# Transformer.net
KiCad netlist of a schematic drawn in Altium Designer
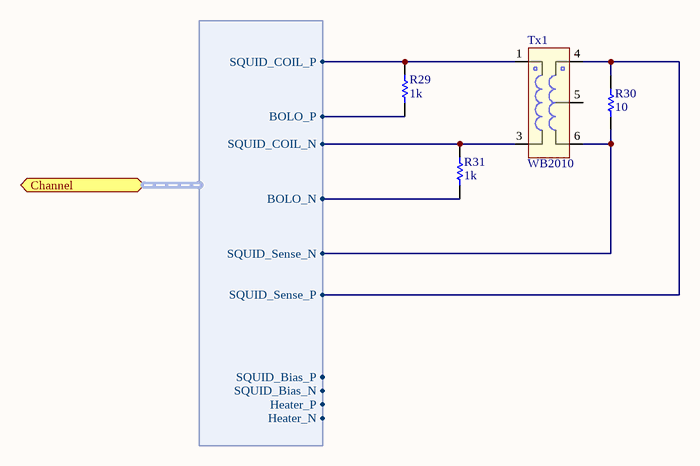
[diagram p0: Transformer.SchDoc]

(export (version "E")
  (design (tool "Eeschema 10.0.6"))
  (components
    (comp (ref "R29")
      (value "1k")
      (footprint "0603")
      (description "1k RES 0603")
      (fields
        (field (name "MANUFACTURER") "Vishay Dale")
        (field (name "MANUFACTURER PART NUMBER") "CRCW06031K00FKEA")
      )
      (libsource (lib "MGNGSQ4_Dongles") (part "RES 0603"))
    )
    (comp (ref "R30")
      (value "10")
      (footprint "0603")
      (description "10 Ohm RES 0603")
      (fields
        (field (name "MANUFACTURER") "Vishay Dale")
        (field (name "MANUFACTURER PART NUMBER") "CRCW060310R0FKEA")
      )
      (libsource (lib "MGNGSQ4_Dongles") (part "RES 0603"))
    )
    (comp (ref "R31")
      (value "1k")
      (footprint "0603")
      (description "1k RES 0603")
      (fields
        (field (name "MANUFACTURER") "Vishay Dale")
        (field (name "MANUFACTURER PART NUMBER") "CRCW06031K00FKEA")
      )
      (libsource (lib "MGNGSQ4_Dongles") (part "RES 0603"))
    )
    (comp (ref "Tx1")
      (value "WB2010")
      (footprint "WB2010")
      (description "WB2010 1:1 Transformer")
      (fields
        (field (name "MANUFACTURER") "Coilcraft")
        (field (name "MANUFACTURER PART NUMBER") "WB2010-SMLB")
      )
      (libsource (lib "MGNGSQ4_Dongles") (part "WB2010"))
    )
  )
  (nets
    (net (code "2") (name "/BOLO_N") (class "Default")
      (node (ref "R31") (pin "1") (pinfunction "1_1") (pintype "passive"))
    )
    (net (code "3") (name "/BOLO_P") (class "Default")
      (node (ref "R29") (pin "1") (pinfunction "1_1") (pintype "passive"))
    )
    (net (code "4") (name "/SQUID_COIL_N") (class "Default")
      (node (ref "R31") (pin "2") (pinfunction "2_2") (pintype "passive"))
      (node (ref "Tx1") (pin "3") (pinfunction "3_3") (pintype "passive"))
    )
    (net (code "5") (name "/SQUID_COIL_P") (class "Default")
      (node (ref "R29") (pin "2") (pinfunction "2_2") (pintype "passive"))
      (node (ref "Tx1") (pin "1") (pinfunction "1_1") (pintype "passive"))
    )
    (net (code "6") (name "/SQUID_Sense_N") (class "Default")
      (node (ref "R30") (pin "1") (pinfunction "1_1") (pintype "passive"))
      (node (ref "Tx1") (pin "6") (pinfunction "6_6") (pintype "passive"))
    )
    (net (code "7") (name "/SQUID_Sense_P") (class "Default")
      (node (ref "R30") (pin "2") (pinfunction "2_2") (pintype "passive"))
      (node (ref "Tx1") (pin "4") (pinfunction "4_4") (pintype "passive"))
    )
    (net (code "9") (name "unconnected-(Tx1-Pad5)") (class "Default")
      (node (ref "Tx1") (pin "5") (pinfunction "5_5") (pintype "passive"))
    )
  )
)
